# nixieClock.net
KiCad netlist of a schematic drawn in EAGLE
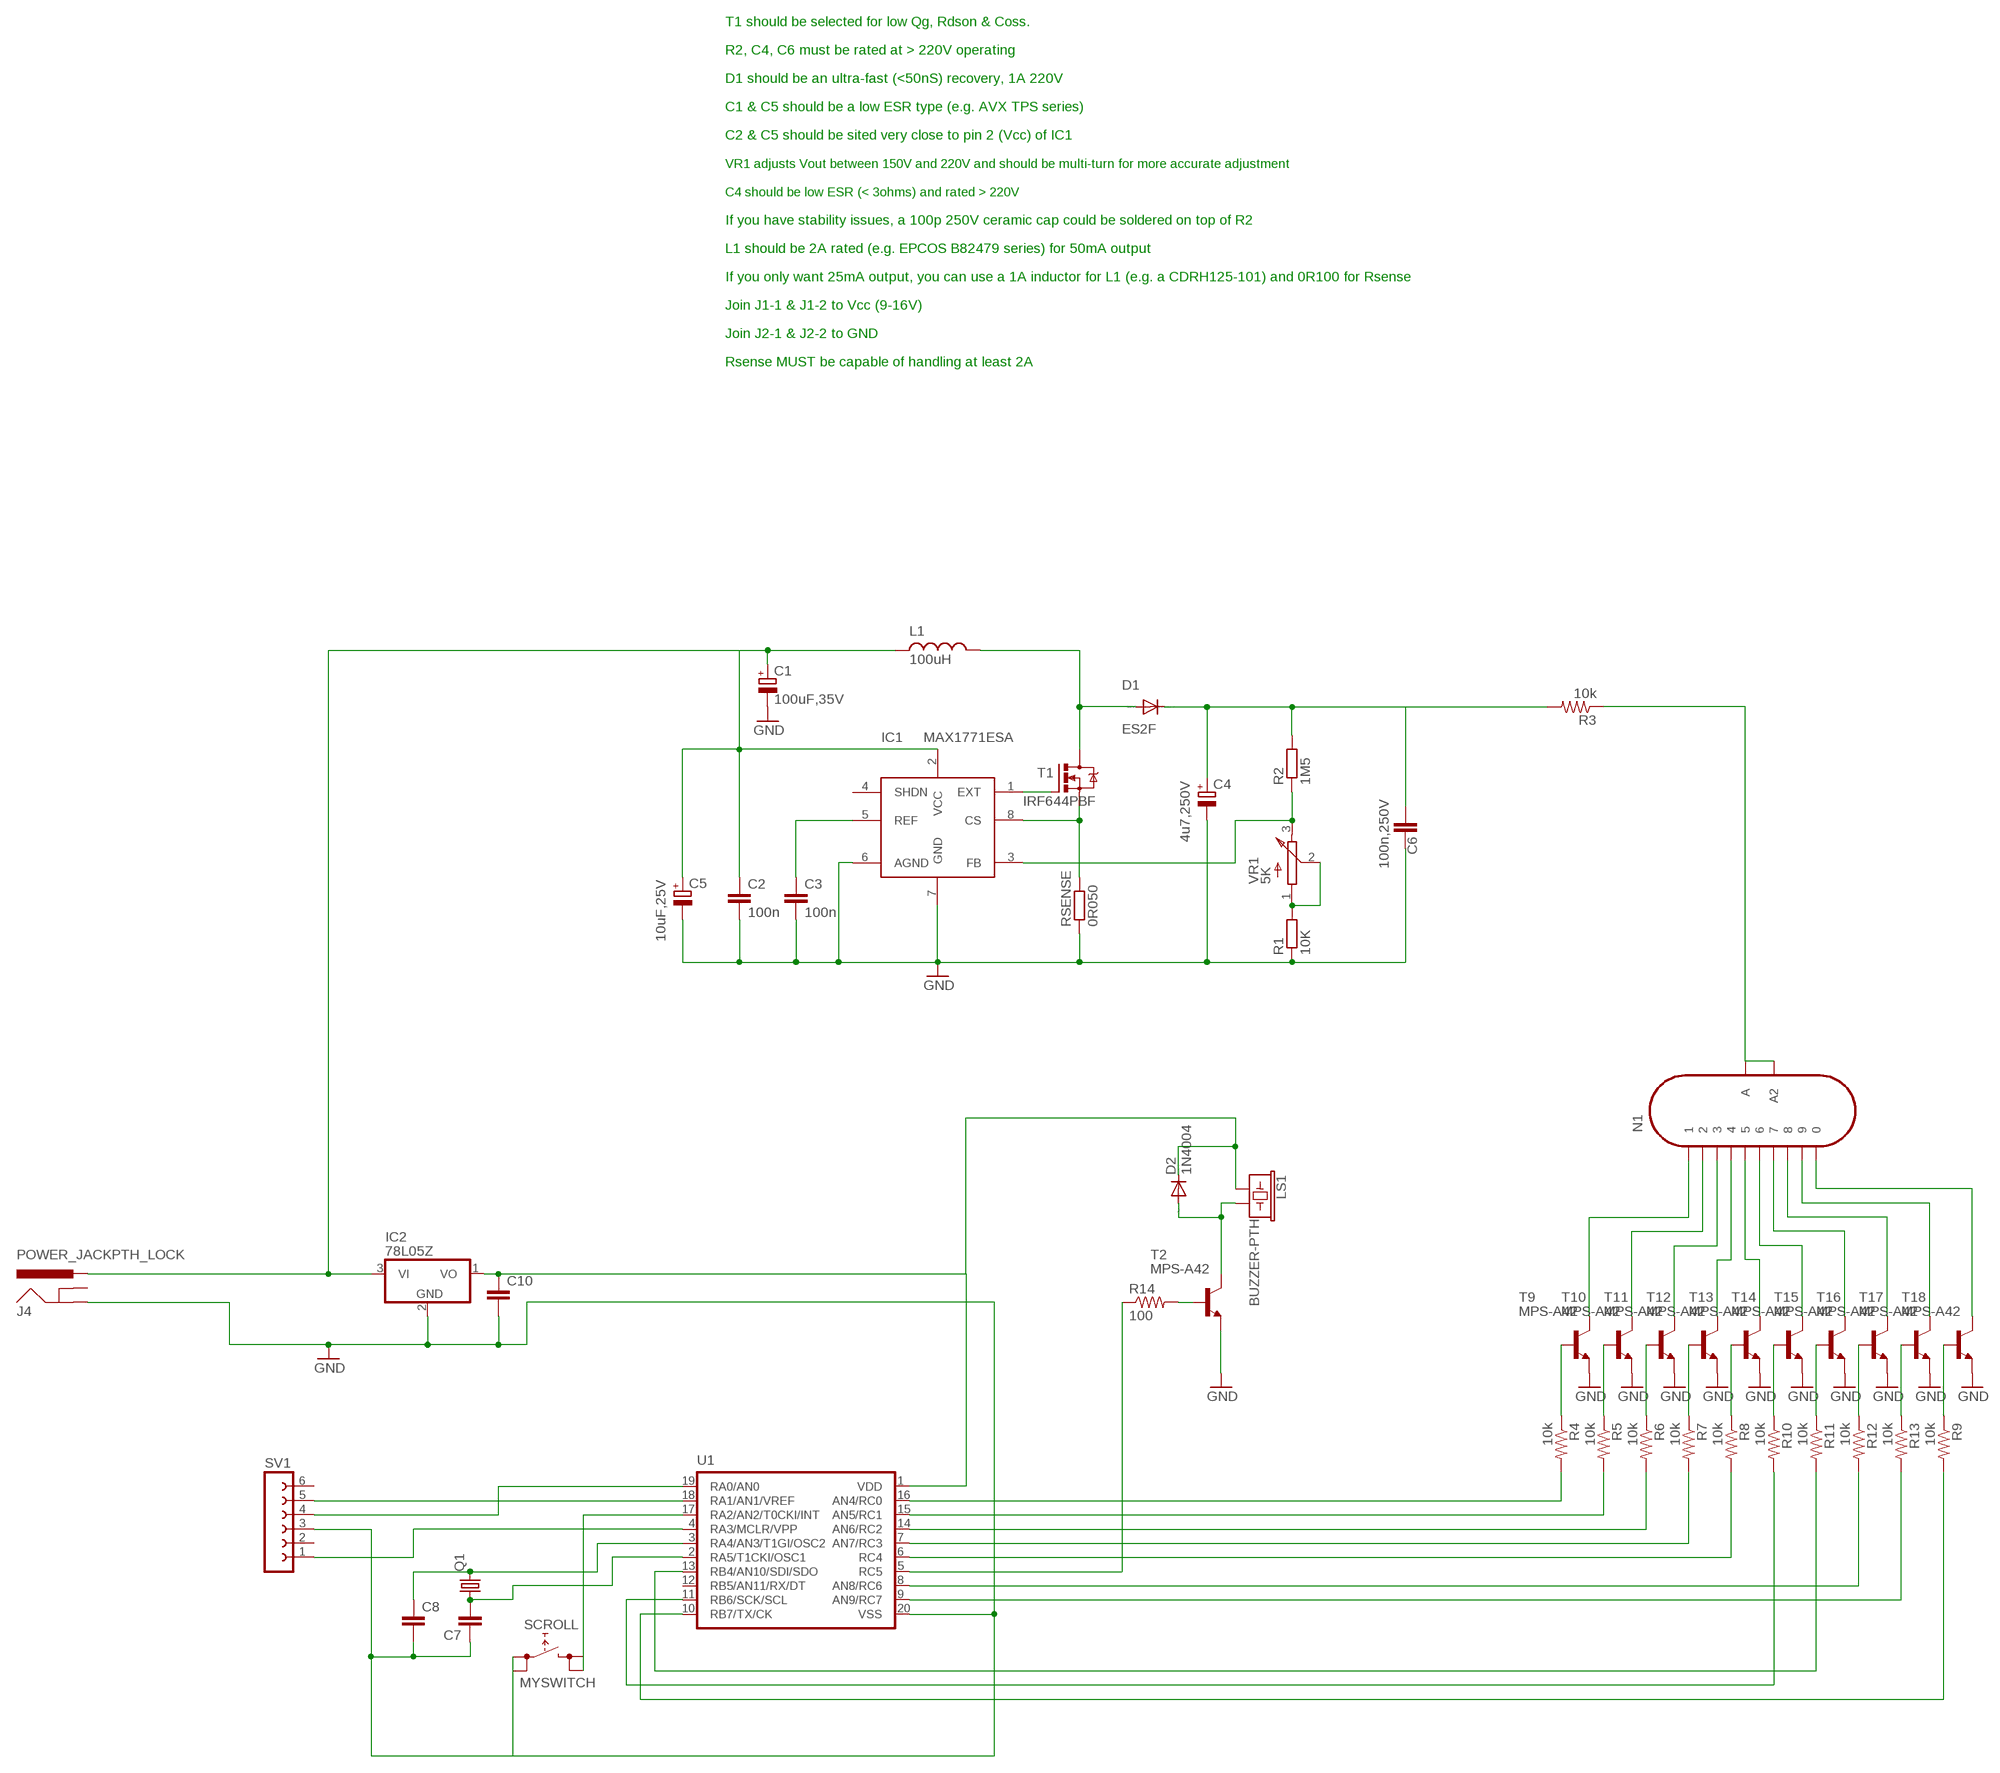
[diagram p0: schematic, sheet 1]

(export (version "E")
  (design (tool "Eeschema 10.0.6"))
  (components
    (comp (ref "C1")
      (value "100uF,35V")
      (footprint "eagle-import:C-EIA-7343")
      (libsource (lib "eagle-import") (part "C-POL-EU7343"))
    )
    (comp (ref "C2")
      (value "100n")
      (footprint "eagle-import:C0805")
      (libsource (lib "eagle-import") (part "C-EUC0805"))
    )
    (comp (ref "C3")
      (value "100n")
      (footprint "eagle-import:C0805")
      (libsource (lib "eagle-import") (part "C-EUC0805"))
    )
    (comp (ref "C4")
      (value "4u7,250V")
      (footprint "eagle-import:NICHICON-UJ-12")
      (libsource (lib "eagle-import") (part "C-POL-EU-NICHICON-UJ-12"))
    )
    (comp (ref "C5")
      (value "10uF,25V")
      (footprint "eagle-import:C-EIA-7343")
      (libsource (lib "eagle-import") (part "C-POL-EU7343"))
    )
    (comp (ref "C6")
      (value "100n,250V")
      (footprint "eagle-import:C2420")
      (libsource (lib "eagle-import") (part "C-EU-2420"))
    )
    (comp (ref "C7")
      (value "C2,5-3")
      (footprint "eagle-import:C2.5-3")
      (libsource (lib "eagle-import") (part "C2,5-3"))
    )
    (comp (ref "C8")
      (value "C2,5-3")
      (footprint "eagle-import:C2.5-3")
      (libsource (lib "eagle-import") (part "C2,5-3"))
    )
    (comp (ref "C10")
      (value "C2,5-3")
      (footprint "eagle-import:C2.5-3")
      (libsource (lib "eagle-import") (part "C2,5-3"))
    )
    (comp (ref "D1")
      (value "ES2F")
      (footprint "eagle-import:SMC")
      (libsource (lib "eagle-import") (part "DIODE-SMC"))
    )
    (comp (ref "D2")
      (value "1N4004")
      (footprint "eagle-import:DO41-10")
      (libsource (lib "eagle-import") (part "1N4004"))
    )
    (comp (ref "IC1")
      (value "MAX1771ESA")
      (footprint "eagle-import:SO-8")
      (libsource (lib "eagle-import") (part "MAX1771ESA"))
    )
    (comp (ref "IC2")
      (value "78L05Z")
      (footprint "eagle-import:TO92")
      (libsource (lib "eagle-import") (part "78ZL05"))
    )
    (comp (ref "J4")
      (value "POWER_JACKPTH_LOCK")
      (footprint "eagle-import:POWER_JACK_PTH_LOCK")
      (libsource (lib "eagle-import") (part "POWER_JACKPTH_LOCK"))
    )
    (comp (ref "L1")
      (value "100uH")
      (footprint "eagle-import:L-B82479")
      (libsource (lib "eagle-import") (part "L-SMT-POWER-B82479"))
    )
    (comp (ref "LS1")
      (value "BUZZER-PTH")
      (footprint "eagle-import:BUZZER-12MM")
      (libsource (lib "eagle-import") (part "BUZZER-PTH"))
    )
    (comp (ref "N1")
      (value "IN-18")
      (footprint "eagle-import:IN-18")
      (libsource (lib "eagle-import") (part "IN-18"))
    )
    (comp (ref "Q1")
      (value "CRYSTALTC26V")
      (footprint "eagle-import:TC26V")
      (libsource (lib "eagle-import") (part "CRYSTALTC26V"))
    )
    (comp (ref "R1")
      (value "10K")
      (footprint "eagle-import:R0805")
      (libsource (lib "eagle-import") (part "R-EU_R0805"))
    )
    (comp (ref "R2")
      (value "1M5")
      (footprint "eagle-import:R2512")
      (libsource (lib "eagle-import") (part "R-EU_R2512"))
    )
    (comp (ref "R3")
      (value "10k")
      (footprint "eagle-import:0207_2V")
      (libsource (lib "eagle-import") (part "R-US_0207/2V"))
    )
    (comp (ref "R4")
      (value "10k")
      (footprint "eagle-import:0207_2V")
      (libsource (lib "eagle-import") (part "R-US_0207/2V"))
    )
    (comp (ref "R5")
      (value "10k")
      (footprint "eagle-import:0207_2V")
      (libsource (lib "eagle-import") (part "R-US_0207/2V"))
    )
    (comp (ref "R6")
      (value "10k")
      (footprint "eagle-import:0207_2V")
      (libsource (lib "eagle-import") (part "R-US_0207/2V"))
    )
    (comp (ref "R7")
      (value "10k")
      (footprint "eagle-import:0207_2V")
      (libsource (lib "eagle-import") (part "R-US_0207/2V"))
    )
    (comp (ref "R8")
      (value "10k")
      (footprint "eagle-import:0207_2V")
      (libsource (lib "eagle-import") (part "R-US_0207/2V"))
    )
    (comp (ref "R9")
      (value "10k")
      (footprint "eagle-import:0207_2V")
      (libsource (lib "eagle-import") (part "R-US_0207/2V"))
    )
    (comp (ref "R10")
      (value "10k")
      (footprint "eagle-import:0207_2V")
      (libsource (lib "eagle-import") (part "R-US_0207/2V"))
    )
    (comp (ref "R11")
      (value "10k")
      (footprint "eagle-import:0207_2V")
      (libsource (lib "eagle-import") (part "R-US_0207/2V"))
    )
    (comp (ref "R12")
      (value "10k")
      (footprint "eagle-import:0207_2V")
      (libsource (lib "eagle-import") (part "R-US_0207/2V"))
    )
    (comp (ref "R13")
      (value "10k")
      (footprint "eagle-import:0207_2V")
      (libsource (lib "eagle-import") (part "R-US_0207/2V"))
    )
    (comp (ref "R14")
      (value "100")
      (footprint "eagle-import:0207_2V")
      (libsource (lib "eagle-import") (part "R-US_0207/2V"))
    )
    (comp (ref "RSENSE")
      (value "0R050")
      (footprint "eagle-import:R2010")
      (libsource (lib "eagle-import") (part "R-EU_R2010"))
    )
    (comp (ref "SCROLL")
      (value "MYSWITCH")
      (footprint "eagle-import:MYSWITCH")
      (libsource (lib "eagle-import") (part "MYSWITCH"))
    )
    (comp (ref "SV1")
      (value "FE06-1")
      (footprint "eagle-import:FE06")
      (libsource (lib "eagle-import") (part "FE06-1"))
    )
    (comp (ref "T1")
      (value "IRF644PBF")
      (footprint "eagle-import:TO220BV")
      (libsource (lib "eagle-import") (part "IRF740"))
    )
    (comp (ref "T2")
      (value "MPS-A42")
      (footprint "eagle-import:TO92-CBE")
      (libsource (lib "eagle-import") (part "-NPN-TO92-CBEMPSA42"))
    )
    (comp (ref "T9")
      (value "MPS-A42")
      (footprint "eagle-import:TO92-CBE")
      (libsource (lib "eagle-import") (part "-NPN-TO92-CBEMPSA42"))
    )
    (comp (ref "T10")
      (value "MPS-A42")
      (footprint "eagle-import:TO92-CBE")
      (libsource (lib "eagle-import") (part "-NPN-TO92-CBEMPSA42"))
    )
    (comp (ref "T11")
      (value "MPS-A42")
      (footprint "eagle-import:TO92-CBE")
      (libsource (lib "eagle-import") (part "-NPN-TO92-CBEMPSA42"))
    )
    (comp (ref "T12")
      (value "MPS-A42")
      (footprint "eagle-import:TO92-CBE")
      (libsource (lib "eagle-import") (part "-NPN-TO92-CBEMPSA42"))
    )
    (comp (ref "T13")
      (value "MPS-A42")
      (footprint "eagle-import:TO92-CBE")
      (libsource (lib "eagle-import") (part "-NPN-TO92-CBEMPSA42"))
    )
    (comp (ref "T14")
      (value "MPS-A42")
      (footprint "eagle-import:TO92-CBE")
      (libsource (lib "eagle-import") (part "-NPN-TO92-CBEMPSA42"))
    )
    (comp (ref "T15")
      (value "MPS-A42")
      (footprint "eagle-import:TO92-CBE")
      (libsource (lib "eagle-import") (part "-NPN-TO92-CBEMPSA42"))
    )
    (comp (ref "T16")
      (value "MPS-A42")
      (footprint "eagle-import:TO92-CBE")
      (libsource (lib "eagle-import") (part "-NPN-TO92-CBEMPSA42"))
    )
    (comp (ref "T17")
      (value "MPS-A42")
      (footprint "eagle-import:TO92-CBE")
      (libsource (lib "eagle-import") (part "-NPN-TO92-CBEMPSA42"))
    )
    (comp (ref "T18")
      (value "MPS-A42")
      (footprint "eagle-import:TO92-CBE")
      (libsource (lib "eagle-import") (part "-NPN-TO92-CBEMPSA42"))
    )
    (comp (ref "U1")
      (value "PIC16F6XX")
      (footprint "eagle-import:DIL20")
      (libsource (lib "eagle-import") (part "PIC16F6XX"))
    )
    (comp (ref "VR1")
      (value "5K")
      (footprint "eagle-import:BOURNS-3214W")
      (libsource (lib "eagle-import") (part "TRIMPOT-3214W"))
    )
  )
  (nets
    (net (code "1") (name "GND") (class "Default")
      (node (ref "C1") (pin "-") (pinfunction "-_-") (pintype "passive"))
      (node (ref "C10") (pin "2") (pinfunction "2_2") (pintype "passive"))
      (node (ref "C2") (pin "2") (pinfunction "2_2") (pintype "passive"))
      (node (ref "C3") (pin "2") (pinfunction "2_2") (pintype "passive"))
      (node (ref "C4") (pin "1") (pinfunction "-_1") (pintype "passive"))
      (node (ref "C5") (pin "-") (pinfunction "-_-") (pintype "passive"))
      (node (ref "C6") (pin "P$2") (pinfunction "2_P$2") (pintype "passive"))
      (node (ref "C7") (pin "1") (pinfunction "1_1") (pintype "passive"))
      (node (ref "C8") (pin "2") (pinfunction "2_2") (pintype "passive"))
      (node (ref "IC1") (pin "6") (pinfunction "AGND_6") (pintype "input"))
      (node (ref "IC1") (pin "7") (pinfunction "GND_7") (pintype "input"))
      (node (ref "IC2") (pin "2") (pinfunction "GND_2") (pintype "passive"))
      (node (ref "J4") (pin "GND") (pinfunction "GND_GND") (pintype "bidirectional"))
      (node (ref "R1") (pin "1") (pinfunction "1_1") (pintype "passive"))
      (node (ref "RSENSE") (pin "1") (pinfunction "1_1") (pintype "passive"))
      (node (ref "SCROLL") (pin "A0") (pinfunction "0_A0") (pintype "passive"))
      (node (ref "SCROLL") (pin "A1") (pinfunction "0_A1") (pintype "passive"))
      (node (ref "SV1") (pin "3") (pinfunction "3_3") (pintype "passive"))
      (node (ref "T10") (pin "E") (pinfunction "E_E") (pintype "passive"))
      (node (ref "T11") (pin "E") (pinfunction "E_E") (pintype "passive"))
      (node (ref "T12") (pin "E") (pinfunction "E_E") (pintype "passive"))
      (node (ref "T13") (pin "E") (pinfunction "E_E") (pintype "passive"))
      (node (ref "T14") (pin "E") (pinfunction "E_E") (pintype "passive"))
      (node (ref "T15") (pin "E") (pinfunction "E_E") (pintype "passive"))
      (node (ref "T16") (pin "E") (pinfunction "E_E") (pintype "passive"))
      (node (ref "T17") (pin "E") (pinfunction "E_E") (pintype "passive"))
      (node (ref "T18") (pin "E") (pinfunction "E_E") (pintype "passive"))
      (node (ref "T2") (pin "E") (pinfunction "E_E") (pintype "passive"))
      (node (ref "T9") (pin "E") (pinfunction "E_E") (pintype "passive"))
      (node (ref "U1") (pin "20") (pinfunction "VSS_20") (pintype "power_in"))
    )
    (net (code "2") (name "Net-(C4-+)") (class "Default")
      (node (ref "C4") (pin "2") (pinfunction "+_2") (pintype "passive"))
      (node (ref "C6") (pin "P$1") (pinfunction "1_P$1") (pintype "passive"))
      (node (ref "D1") (pin "C") (pinfunction "C_C") (pintype "passive"))
      (node (ref "R2") (pin "2") (pinfunction "2_2") (pintype "passive"))
      (node (ref "R3") (pin "2") (pinfunction "2_2") (pintype "passive"))
    )
    (net (code "3") (name "Net-(IC1-CS)") (class "Default")
      (node (ref "IC1") (pin "8") (pinfunction "CS_8") (pintype "input"))
      (node (ref "RSENSE") (pin "2") (pinfunction "2_2") (pintype "passive"))
      (node (ref "T1") (pin "S") (pinfunction "S_S") (pintype "passive"))
    )
    (net (code "4") (name "Net-(IC1-EXT)") (class "Default")
      (node (ref "IC1") (pin "1") (pinfunction "EXT_1") (pintype "output"))
      (node (ref "T1") (pin "G") (pinfunction "G_G") (pintype "passive"))
    )
    (net (code "5") (name "Net-(IC1-FB)") (class "Default")
      (node (ref "IC1") (pin "3") (pinfunction "FB_3") (pintype "input"))
      (node (ref "R2") (pin "1") (pinfunction "1_1") (pintype "passive"))
      (node (ref "VR1") (pin "3") (pinfunction "B_3") (pintype "passive"))
    )
    (net (code "6") (name "Net-(IC1-REF)") (class "Default")
      (node (ref "C3") (pin "1") (pinfunction "1_1") (pintype "passive"))
      (node (ref "IC1") (pin "5") (pinfunction "REF_5") (pintype "input"))
    )
    (net (code "7") (name "Net-(IC1-VCC)") (class "Default")
      (node (ref "C1") (pin "+") (pinfunction "+_+") (pintype "passive"))
      (node (ref "C2") (pin "1") (pinfunction "1_1") (pintype "passive"))
      (node (ref "C5") (pin "+") (pinfunction "+_+") (pintype "passive"))
      (node (ref "IC1") (pin "2") (pinfunction "VCC_2") (pintype "input"))
      (node (ref "IC2") (pin "3") (pinfunction "VI_3") (pintype "input"))
      (node (ref "J4") (pin "PWR") (pinfunction "PWR_PWR") (pintype "bidirectional"))
      (node (ref "L1") (pin "P$1") (pinfunction "1_P$1") (pintype "passive"))
    )
    (net (code "8") (name "Net-(IC2-VO)") (class "Default")
      (node (ref "C10") (pin "1") (pinfunction "1_1") (pintype "passive"))
      (node (ref "D2") (pin "C") (pinfunction "C_C") (pintype "passive"))
      (node (ref "IC2") (pin "1") (pinfunction "VO_1") (pintype "passive"))
      (node (ref "LS1") (pin "+") (pinfunction "1_+") (pintype "passive"))
      (node (ref "U1") (pin "1") (pinfunction "VDD_1") (pintype "power_in"))
    )
    (net (code "9") (name "Net-(L1-2)") (class "Default")
      (node (ref "D1") (pin "A") (pinfunction "A_A") (pintype "passive"))
      (node (ref "L1") (pin "P$2") (pinfunction "2_P$2") (pintype "passive"))
      (node (ref "T1") (pin "D") (pinfunction "D_D") (pintype "passive"))
    )
    (net (code "10") (name "Net-(LS1-2)") (class "Default")
      (node (ref "D2") (pin "A") (pinfunction "A_A") (pintype "passive"))
      (node (ref "LS1") (pin "-") (pinfunction "2_-") (pintype "passive"))
      (node (ref "T2") (pin "C") (pinfunction "C_C") (pintype "passive"))
    )
    (net (code "11") (name "Net-(N1-Pad0)") (class "Default")
      (node (ref "N1") (pin "0") (pinfunction "0_0") (pintype "bidirectional"))
      (node (ref "T18") (pin "C") (pinfunction "C_C") (pintype "passive"))
    )
    (net (code "12") (name "Net-(N1-Pad1)") (class "Default")
      (node (ref "N1") (pin "1") (pinfunction "1_1") (pintype "bidirectional"))
      (node (ref "T9") (pin "C") (pinfunction "C_C") (pintype "passive"))
    )
    (net (code "13") (name "Net-(N1-Pad2)") (class "Default")
      (node (ref "N1") (pin "2") (pinfunction "2_2") (pintype "bidirectional"))
      (node (ref "T10") (pin "C") (pinfunction "C_C") (pintype "passive"))
    )
    (net (code "14") (name "Net-(N1-Pad3)") (class "Default")
      (node (ref "N1") (pin "3") (pinfunction "3_3") (pintype "bidirectional"))
      (node (ref "T11") (pin "C") (pinfunction "C_C") (pintype "passive"))
    )
    (net (code "15") (name "Net-(N1-Pad4)") (class "Default")
      (node (ref "N1") (pin "4") (pinfunction "4_4") (pintype "bidirectional"))
      (node (ref "T12") (pin "C") (pinfunction "C_C") (pintype "passive"))
    )
    (net (code "16") (name "Net-(N1-Pad5)") (class "Default")
      (node (ref "N1") (pin "5") (pinfunction "5_5") (pintype "bidirectional"))
      (node (ref "T13") (pin "C") (pinfunction "C_C") (pintype "passive"))
    )
    (net (code "17") (name "Net-(N1-Pad6)") (class "Default")
      (node (ref "N1") (pin "6") (pinfunction "6_6") (pintype "bidirectional"))
      (node (ref "T14") (pin "C") (pinfunction "C_C") (pintype "passive"))
    )
    (net (code "18") (name "Net-(N1-Pad7)") (class "Default")
      (node (ref "N1") (pin "7") (pinfunction "7_7") (pintype "bidirectional"))
      (node (ref "T15") (pin "C") (pinfunction "C_C") (pintype "passive"))
    )
    (net (code "19") (name "Net-(N1-Pad8)") (class "Default")
      (node (ref "N1") (pin "8") (pinfunction "8_8") (pintype "bidirectional"))
      (node (ref "T16") (pin "C") (pinfunction "C_C") (pintype "passive"))
    )
    (net (code "20") (name "Net-(N1-Pad9)") (class "Default")
      (node (ref "N1") (pin "9") (pinfunction "9_9") (pintype "bidirectional"))
      (node (ref "T17") (pin "C") (pinfunction "C_C") (pintype "passive"))
    )
    (net (code "21") (name "Net-(N1-PadA)") (class "Default")
      (node (ref "N1") (pin "A") (pinfunction "A_A") (pintype "bidirectional"))
      (node (ref "N1") (pin "A2") (pinfunction "A2_A2") (pintype "bidirectional"))
      (node (ref "R3") (pin "1") (pinfunction "1_1") (pintype "passive"))
    )
    (net (code "22") (name "Net-(R4-Pad1)") (class "Default")
      (node (ref "R4") (pin "1") (pinfunction "1_1") (pintype "passive"))
      (node (ref "T9") (pin "B") (pinfunction "B_B") (pintype "passive"))
    )
    (net (code "23") (name "Net-(R5-Pad1)") (class "Default")
      (node (ref "R5") (pin "1") (pinfunction "1_1") (pintype "passive"))
      (node (ref "T10") (pin "B") (pinfunction "B_B") (pintype "passive"))
    )
    (net (code "24") (name "Net-(R6-Pad1)") (class "Default")
      (node (ref "R6") (pin "1") (pinfunction "1_1") (pintype "passive"))
      (node (ref "T11") (pin "B") (pinfunction "B_B") (pintype "passive"))
    )
    (net (code "25") (name "Net-(R7-Pad1)") (class "Default")
      (node (ref "R7") (pin "1") (pinfunction "1_1") (pintype "passive"))
      (node (ref "T12") (pin "B") (pinfunction "B_B") (pintype "passive"))
    )
    (net (code "26") (name "Net-(R8-Pad1)") (class "Default")
      (node (ref "R8") (pin "1") (pinfunction "1_1") (pintype "passive"))
      (node (ref "T13") (pin "B") (pinfunction "B_B") (pintype "passive"))
    )
    (net (code "27") (name "Net-(R9-Pad1)") (class "Default")
      (node (ref "R9") (pin "1") (pinfunction "1_1") (pintype "passive"))
      (node (ref "T18") (pin "B") (pinfunction "B_B") (pintype "passive"))
    )
    (net (code "28") (name "Net-(R10-Pad1)") (class "Default")
      (node (ref "R10") (pin "1") (pinfunction "1_1") (pintype "passive"))
      (node (ref "T14") (pin "B") (pinfunction "B_B") (pintype "passive"))
    )
    (net (code "29") (name "Net-(R11-Pad1)") (class "Default")
      (node (ref "R11") (pin "1") (pinfunction "1_1") (pintype "passive"))
      (node (ref "T15") (pin "B") (pinfunction "B_B") (pintype "passive"))
    )
    (net (code "30") (name "Net-(R12-Pad1)") (class "Default")
      (node (ref "R12") (pin "1") (pinfunction "1_1") (pintype "passive"))
      (node (ref "T16") (pin "B") (pinfunction "B_B") (pintype "passive"))
    )
    (net (code "31") (name "Net-(R13-Pad1)") (class "Default")
      (node (ref "R13") (pin "1") (pinfunction "1_1") (pintype "passive"))
      (node (ref "T17") (pin "B") (pinfunction "B_B") (pintype "passive"))
    )
    (net (code "32") (name "Net-(R14-Pad2)") (class "Default")
      (node (ref "R14") (pin "2") (pinfunction "2_2") (pintype "passive"))
      (node (ref "T2") (pin "B") (pinfunction "B_B") (pintype "passive"))
    )
    (net (code "33") (name "Net-(U1-AN4{slash}RC0)") (class "Default")
      (node (ref "R4") (pin "2") (pinfunction "2_2") (pintype "passive"))
      (node (ref "U1") (pin "16") (pinfunction "AN4/RC0_16") (pintype "bidirectional"))
    )
    (net (code "34") (name "Net-(U1-AN5{slash}RC1)") (class "Default")
      (node (ref "R5") (pin "2") (pinfunction "2_2") (pintype "passive"))
      (node (ref "U1") (pin "15") (pinfunction "AN5/RC1_15") (pintype "bidirectional"))
    )
    (net (code "35") (name "Net-(U1-AN6{slash}RC2)") (class "Default")
      (node (ref "R6") (pin "2") (pinfunction "2_2") (pintype "passive"))
      (node (ref "U1") (pin "14") (pinfunction "AN6/RC2_14") (pintype "bidirectional"))
    )
    (net (code "36") (name "Net-(U1-AN7{slash}RC3)") (class "Default")
      (node (ref "R7") (pin "2") (pinfunction "2_2") (pintype "passive"))
      (node (ref "U1") (pin "7") (pinfunction "AN7/RC3_7") (pintype "bidirectional"))
    )
    (net (code "37") (name "Net-(U1-AN8{slash}RC6)") (class "Default")
      (node (ref "R12") (pin "2") (pinfunction "2_2") (pintype "passive"))
      (node (ref "U1") (pin "8") (pinfunction "AN8/RC6_8") (pintype "bidirectional"))
    )
    (net (code "38") (name "Net-(U1-AN9{slash}RC7)") (class "Default")
      (node (ref "R13") (pin "2") (pinfunction "2_2") (pintype "passive"))
      (node (ref "U1") (pin "9") (pinfunction "AN9/RC7_9") (pintype "bidirectional"))
    )
    (net (code "39") (name "Net-(U1-RA0{slash}AN0)") (class "Default")
      (node (ref "SV1") (pin "4") (pinfunction "4_4") (pintype "passive"))
      (node (ref "U1") (pin "19") (pinfunction "RA0/AN0_19") (pintype "bidirectional"))
    )
    (net (code "40") (name "Net-(U1-RA1{slash}AN1{slash}VREF)") (class "Default")
      (node (ref "SV1") (pin "5") (pinfunction "5_5") (pintype "passive"))
      (node (ref "U1") (pin "18") (pinfunction "RA1/AN1/VREF_18") (pintype "bidirectional"))
    )
    (net (code "41") (name "Net-(U1-RA2{slash}AN2{slash}T0CKI{slash}INT)") (class "Default")
      (node (ref "SCROLL") (pin "B0") (pinfunction "1_B0") (pintype "passive"))
      (node (ref "SCROLL") (pin "B1") (pinfunction "1_B1") (pintype "passive"))
      (node (ref "U1") (pin "17") (pinfunction "RA2/AN2/T0CKI/INT_17") (pintype "bidirectional"))
    )
    (net (code "42") (name "Net-(U1-RA3{slash}MCLR{slash}VPP)") (class "Default")
      (node (ref "SV1") (pin "1") (pinfunction "1_1") (pintype "passive"))
      (node (ref "U1") (pin "4") (pinfunction "RA3/MCLR/VPP_4") (pintype "input"))
    )
    (net (code "43") (name "Net-(U1-RA4{slash}AN3{slash}T1GI{slash}OSC2)") (class "Default")
      (node (ref "C8") (pin "1") (pinfunction "1_1") (pintype "passive"))
      (node (ref "Q1") (pin "2") (pinfunction "2_2") (pintype "passive"))
      (node (ref "U1") (pin "3") (pinfunction "RA4/AN3/T1GI/OSC2_3") (pintype "bidirectional"))
    )
    (net (code "44") (name "Net-(U1-RA5{slash}T1CKI{slash}OSC1)") (class "Default")
      (node (ref "C7") (pin "2") (pinfunction "2_2") (pintype "passive"))
      (node (ref "Q1") (pin "1") (pinfunction "1_1") (pintype "passive"))
      (node (ref "U1") (pin "2") (pinfunction "RA5/T1CKI/OSC1_2") (pintype "bidirectional"))
    )
    (net (code "45") (name "Net-(U1-RB4{slash}AN10{slash}SDI{slash}SDO)") (class "Default")
      (node (ref "R11") (pin "2") (pinfunction "2_2") (pintype "passive"))
      (node (ref "U1") (pin "13") (pinfunction "RB4/AN10/SDI/SDO_13") (pintype "bidirectional"))
    )
    (net (code "46") (name "Net-(U1-RB6{slash}SCK{slash}SCL)") (class "Default")
      (node (ref "R10") (pin "2") (pinfunction "2_2") (pintype "passive"))
      (node (ref "U1") (pin "11") (pinfunction "RB6/SCK/SCL_11") (pintype "bidirectional"))
    )
    (net (code "47") (name "Net-(U1-RB7{slash}TX{slash}CK)") (class "Default")
      (node (ref "R9") (pin "2") (pinfunction "2_2") (pintype "passive"))
      (node (ref "U1") (pin "10") (pinfunction "RB7/TX/CK_10") (pintype "bidirectional"))
    )
    (net (code "48") (name "Net-(U1-RC4)") (class "Default")
      (node (ref "R8") (pin "2") (pinfunction "2_2") (pintype "passive"))
      (node (ref "U1") (pin "6") (pinfunction "RC4_6") (pintype "bidirectional"))
    )
    (net (code "49") (name "Net-(U1-RC5)") (class "Default")
      (node (ref "R14") (pin "1") (pinfunction "1_1") (pintype "passive"))
      (node (ref "U1") (pin "5") (pinfunction "RC5_5") (pintype "bidirectional"))
    )
    (net (code "50") (name "Net-(VR1-A)") (class "Default")
      (node (ref "R1") (pin "2") (pinfunction "2_2") (pintype "passive"))
      (node (ref "VR1") (pin "1") (pinfunction "A_1") (pintype "passive"))
      (node (ref "VR1") (pin "2") (pinfunction "W_2") (pintype "passive"))
    )
    (net (code "51") (name "unconnected-(IC1-SHDN-Pad4)") (class "Default")
      (node (ref "IC1") (pin "4") (pinfunction "SHDN_4") (pintype "input"))
    )
    (net (code "52") (name "unconnected-(J4-PadGNDBREAK)") (class "Default")
      (node (ref "J4") (pin "GNDBREAK") (pinfunction "GNDBREAK_GNDBREAK") (pintype "bidirectional"))
    )
    (net (code "53") (name "unconnected-(SV1-Pad2)") (class "Default")
      (node (ref "SV1") (pin "2") (pinfunction "2_2") (pintype "passive"))
    )
    (net (code "54") (name "unconnected-(SV1-Pad6)") (class "Default")
      (node (ref "SV1") (pin "6") (pinfunction "6_6") (pintype "passive"))
    )
    (net (code "55") (name "unconnected-(U1-RB5{slash}AN11{slash}RX{slash}DT-Pad12)") (class "Default")
      (node (ref "U1") (pin "12") (pinfunction "RB5/AN11/RX/DT_12") (pintype "bidirectional"))
    )
  )
)
